# Sheet1.net
KiCad netlist of a schematic drawn in Altium Designer
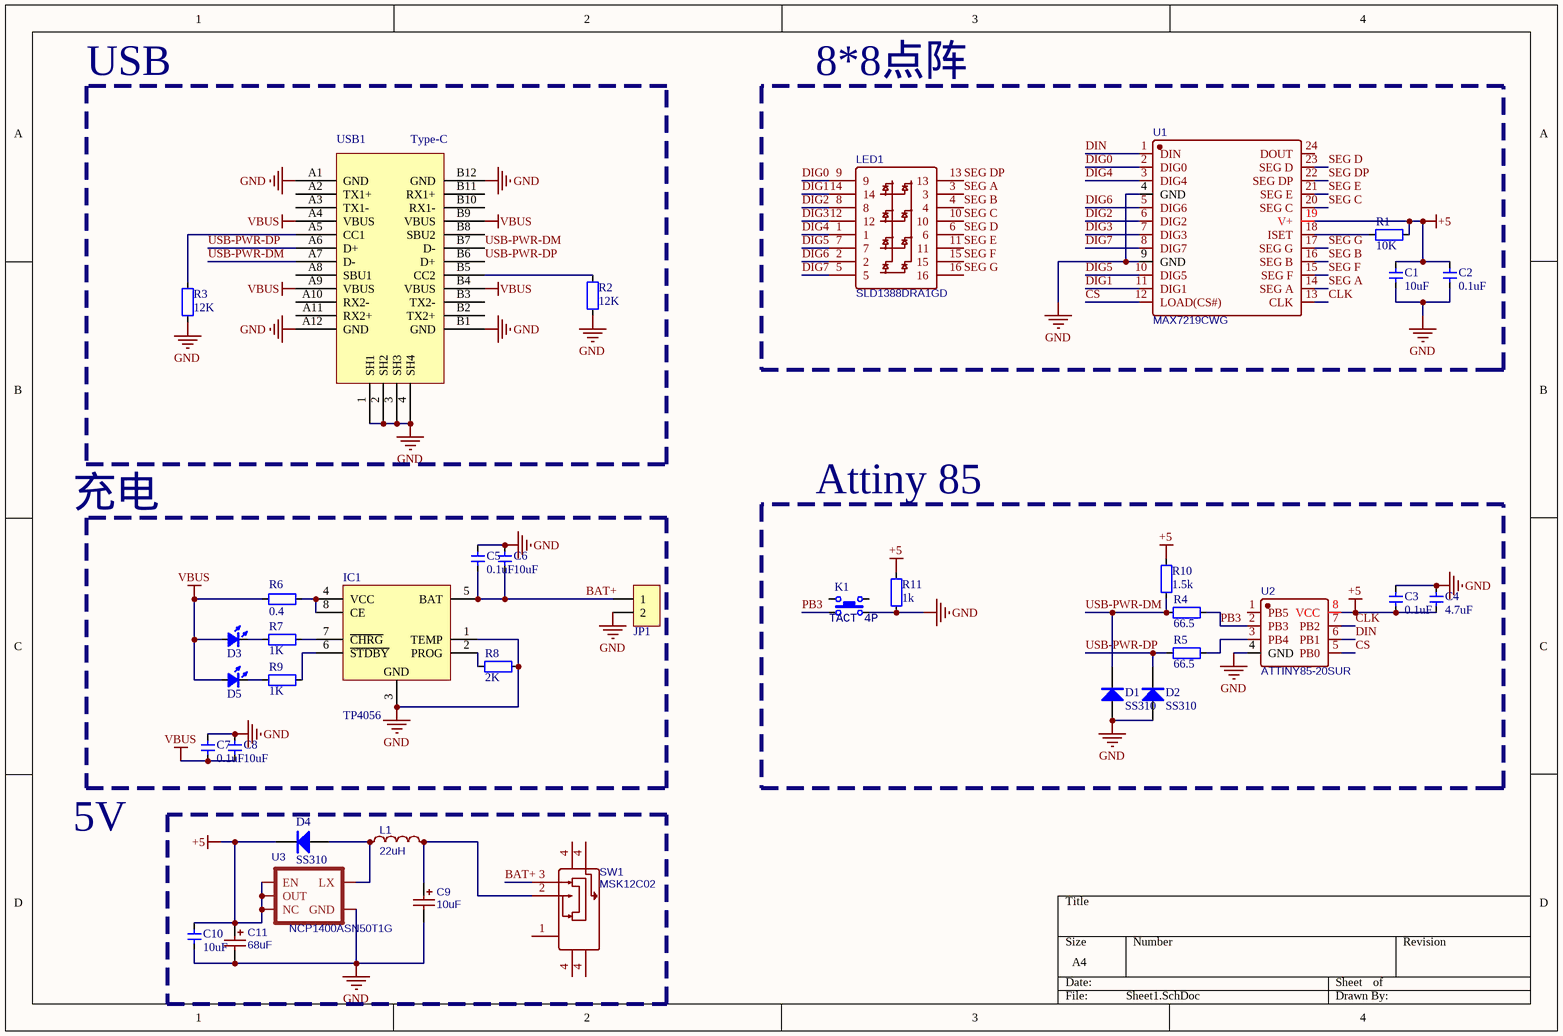
[diagram p0: Sheet1.SchDoc]

(export (version "E")
  (design (tool "Eeschema 10.0.6"))
  (components
    (comp (ref "C1")
      (value "10uF")
      (footprint "CAP_0402")
      (description "Capacitor")
      (libsource (lib "88DianZhen") (part "电容-0402"))
    )
    (comp (ref "C2")
      (value "0.1uF")
      (footprint "CAP_0402")
      (description "Capacitor")
      (libsource (lib "88DianZhen") (part "电容-0402"))
    )
    (comp (ref "C3")
      (value "0.1uF")
      (footprint "CAP_0402")
      (description "Capacitor")
      (libsource (lib "88DianZhen") (part "电容-0402"))
    )
    (comp (ref "C4")
      (value "4.7uF")
      (footprint "CAP_0402")
      (description "Capacitor")
      (libsource (lib "88DianZhen") (part "电容-0402"))
    )
    (comp (ref "C5")
      (value "0.1uF")
      (footprint "CAP_0402")
      (description "Capacitor")
      (libsource (lib "88DianZhen") (part "电容-0402"))
    )
    (comp (ref "C6")
      (value "10uF")
      (footprint "CAP_0402")
      (description "Capacitor")
      (libsource (lib "88DianZhen") (part "电容-0402"))
    )
    (comp (ref "C7")
      (value "0.1uF")
      (footprint "CAP_0402")
      (description "Capacitor")
      (libsource (lib "88DianZhen") (part "电容-0402"))
    )
    (comp (ref "C8")
      (value "10uF")
      (footprint "CAP_0402")
      (description "Capacitor")
      (libsource (lib "88DianZhen") (part "电容-0402"))
    )
    (comp (ref "C9")
      (value "10uF")
      (footprint "CAP-SMD_L3.2-W1.6-RD")
      (fields
        (field (name "BOM_MANUFACTURER PART") "CA45-A010M106T")
        (field (name "BOM_SUPPLIER PART") "C127946")
        (field (name "CONTRIBUTOR") "LCSC")
      )
      (libsource (lib "88DianZhen") (part "钽电容"))
    )
    (comp (ref "C10")
      (value "10uF")
      (footprint "CAP_0402")
      (description "Capacitor")
      (libsource (lib "88DianZhen") (part "电容-0402"))
    )
    (comp (ref "C11")
      (value "68uF")
      (footprint "CAP-SMD_L3.5-W2.8")
      (fields
        (field (name "BOM_MANUFACTURER PART") "CA45-A010M106T")
        (field (name "BOM_SUPPLIER PART") "C127946")
        (field (name "CONTRIBUTOR") "LCSC")
      )
      (libsource (lib "88DianZhen") (part "钽电容"))
    )
    (comp (ref "D1")
      (value "SS310")
      (footprint "SMA")
      (description "肖特基二极管")
      (fields (field (name "版权归属") "源创客"))
      (libsource (lib "88DianZhen") (part "SS210"))
    )
    (comp (ref "D2")
      (value "SS310")
      (footprint "SMA")
      (description "肖特基二极管")
      (fields (field (name "版权归属") "源创客"))
      (libsource (lib "88DianZhen") (part "SS210"))
    )
    (comp (ref "D3")
      (value "color?")
      (footprint "LED_0402_RED")
      (description "LED")
      (libsource (lib "88DianZhen") (part "LED_0402"))
    )
    (comp (ref "D4")
      (value "SS310")
      (footprint "SMA")
      (description "肖特基二极管")
      (fields (field (name "版权归属") "源创客"))
      (libsource (lib "88DianZhen") (part "二极管"))
    )
    (comp (ref "D5")
      (value "color?")
      (footprint "LED_0402_RED")
      (description "LED")
      (libsource (lib "88DianZhen") (part "LED_0402"))
    )
    (comp (ref "IC1")
      (value "TP4056")
      (footprint "PcbLib1:SOP8")
      (description "锂电池充电管理")
      (fields (field (name "版权归属") "源创客"))
      (libsource (lib "88DianZhen") (part "TP4056"))
    )
    (comp (ref "JP1")
      (value "HDR-1X2")
      (footprint "KF2EDGK-2.54-LI-2P")
      (description "2P接插件")
      (fields (field (name "版权归属") "源创客"))
      (libsource (lib "88DianZhen") (part "Header 2"))
    )
    (comp (ref "K1")
      (value "TACT 4P")
      (footprint "ButtonTACT_3.5*3.55_90")
      (description "Button")
      (fields (field (name "TYPE") "TACT 4P"))
      (libsource (lib "88DianZhen") (part "ButtonTACT"))
    )
    (comp (ref "L1")
      (value "22uH")
      (footprint "IND-SMD_L4.5-W4.0_SCD0403T")
      (fields
        (field (name "BOM_SUPPLIER PART") "C304283")
        (field (name "BOM_MANUFACTURER PART") "FPI0403F-220M")
        (field (name "CONTRIBUTOR") "LCSC")
      )
      (libsource (lib "88DianZhen") (part "电感"))
    )
    (comp (ref "LED1")
      (value "SLD1388DRA1GD")
      (footprint "8*8点阵")
      (fields (field (name "BOM_SUPPLIER PART") "C225991") (field (name "CONTRIBUTOR") "LCSC"))
      (libsource (lib "88DianZhen") (part "SLD1388DRA1GD"))
    )
    (comp (ref "R1")
      (value "10K")
      (footprint "R_0402")
      (description "Resistor")
      (libsource (lib "") (part "电阻-0402_1"))
    )
    (comp (ref "R2")
      (value "12K")
      (footprint "R_0402")
      (description "Resistor")
      (libsource (lib "88DianZhen") (part "电阻-0402"))
    )
    (comp (ref "R3")
      (value "12K")
      (footprint "R_0402")
      (description "Resistor")
      (libsource (lib "88DianZhen") (part "电阻-0402"))
    )
    (comp (ref "R4")
      (value "66.5")
      (footprint "0603R")
      (description "Resistor")
      (libsource (lib "") (part "电阻-0402_1"))
    )
    (comp (ref "R5")
      (value "66.5")
      (footprint "0603R")
      (description "Resistor")
      (libsource (lib "") (part "电阻-0402_1"))
    )
    (comp (ref "R6")
      (value "0.4")
      (footprint "1210R")
      (description "Resistor")
      (libsource (lib "") (part "电阻-0402_3"))
    )
    (comp (ref "R7")
      (value "1K")
      (footprint "R_0402")
      (description "Resistor")
      (libsource (lib "") (part "电阻-0402_1"))
    )
    (comp (ref "R8")
      (value "2K")
      (footprint "R_0402")
      (description "Resistor")
      (libsource (lib "") (part "电阻-0402_1"))
    )
    (comp (ref "R9")
      (value "1K")
      (footprint "R_0402")
      (description "Resistor")
      (libsource (lib "") (part "电阻-0402_1"))
    )
    (comp (ref "R10")
      (value "1.5k")
      (footprint "R_0402")
      (description "Resistor")
      (libsource (lib "") (part "电阻-0402_2"))
    )
    (comp (ref "R11")
      (value "1k")
      (footprint "R_0402")
      (description "Resistor")
      (libsource (lib "") (part "电阻-0402_2"))
    )
    (comp (ref "SW1")
      (value "MSK12C02")
      (footprint "SW-TH_MSK12C02")
      (fields (field (name "BOM_SUPPLIER PART") "C431540") (field (name "CONTRIBUTOR") "LCSC"))
      (libsource (lib "88DianZhen") (part "MSK12C02"))
    )
    (comp (ref "U1")
      (value "MAX7219CWG")
      (footprint "SOIC-24_L15.4-W7.5-P1.27-LS10.3-BL")
      (fields (field (name "BOM_SUPPLIER PART") "C9964"))
      (libsource (lib "88DianZhen") (part "MAX7219CWG"))
    )
    (comp (ref "U2")
      (value "ATTINY85-20SUR")
      (footprint "SOIC-8_L5.3-W5.3-P1.27-LS8.2-BL")
      (fields (field (name "BOM_SUPPLIER PART") "C2693737") (field (name "CONTRIBUTOR") "LCSC"))
      (libsource (lib "88DianZhen") (part "ATTINY85-20SUR"))
    )
    (comp (ref "U3")
      (value "NCP1400ASN50T1G")
      (footprint "SOT23-5")
      (fields (field (name "CONTRIBUTOR") "SparkFun"))
      (libsource (lib "88DianZhen") (part "NCP1400ASN50T1G"))
    )
    (comp (ref "USB1")
      (value "Type-C")
      (footprint "Type-C-TOP")
      (libsource (lib "88DianZhen") (part "USB-Type-C-TOP"))
    )
  )
  (nets
    (net (code "1") (name "+5") (class "Default")
      (node (ref "C1") (pin "2") (pinfunction "2_2") (pintype "passive"))
      (node (ref "C10") (pin "2") (pinfunction "2_2") (pintype "passive"))
      (node (ref "C11") (pin "1") (pinfunction "1_1") (pintype "passive"))
      (node (ref "C2") (pin "2") (pinfunction "2_2") (pintype "passive"))
      (node (ref "C3") (pin "1") (pinfunction "1_1") (pintype "passive"))
      (node (ref "C4") (pin "1") (pinfunction "1_1") (pintype "passive"))
      (node (ref "D4") (pin "2") (pinfunction "K_2") (pintype "passive"))
      (node (ref "R1") (pin "2") (pinfunction "2_2") (pintype "passive"))
      (node (ref "R10") (pin "2") (pinfunction "2_2") (pintype "passive"))
      (node (ref "R11") (pin "2") (pinfunction "2_2") (pintype "passive"))
      (node (ref "U1") (pin "19") (pinfunction "V+_19") (pintype "passive"))
      (node (ref "U2") (pin "8") (pinfunction "VCC_8") (pintype "passive"))
      (node (ref "U3") (pin "1") (pinfunction "EN_1") (pintype "passive"))
      (node (ref "U3") (pin "2") (pinfunction "OUT_2") (pintype "passive"))
      (node (ref "U3") (pin "3") (pinfunction "NC_3") (pintype "passive"))
    )
    (net (code "2") (name "/BAT+") (class "Default")
      (node (ref "C5") (pin "1") (pinfunction "1_1") (pintype "passive"))
      (node (ref "C6") (pin "1") (pinfunction "1_1") (pintype "passive"))
      (node (ref "IC1") (pin "5") (pinfunction "BAT_5") (pintype "passive"))
      (node (ref "JP1") (pin "1") (pinfunction "1_1") (pintype "passive"))
      (node (ref "SW1") (pin "3") (pinfunction "3_3") (pintype "passive"))
    )
    (net (code "3") (name "/CLK") (class "Default")
      (node (ref "U1") (pin "13") (pinfunction "CLK_13") (pintype "passive"))
      (node (ref "U2") (pin "7") (pinfunction "PB2_7") (pintype "passive"))
    )
    (net (code "4") (name "/CS") (class "Default")
      (node (ref "U1") (pin "12") (pinfunction "LOAD(CS#)_12") (pintype "passive"))
      (node (ref "U2") (pin "5") (pinfunction "PB0_5") (pintype "passive"))
    )
    (net (code "5") (name "/DIG0") (class "Default")
      (node (ref "LED1") (pin "9") (pinfunction "9_9") (pintype "passive"))
      (node (ref "U1") (pin "2") (pinfunction "DIG0_2") (pintype "passive"))
    )
    (net (code "6") (name "/DIG1") (class "Default")
      (node (ref "LED1") (pin "14") (pinfunction "14_14") (pintype "passive"))
      (node (ref "U1") (pin "11") (pinfunction "DIG1_11") (pintype "passive"))
    )
    (net (code "7") (name "/DIG2") (class "Default")
      (node (ref "LED1") (pin "8") (pinfunction "8_8") (pintype "passive"))
      (node (ref "U1") (pin "6") (pinfunction "DIG2_6") (pintype "passive"))
    )
    (net (code "8") (name "/DIG3") (class "Default")
      (node (ref "LED1") (pin "12") (pinfunction "12_12") (pintype "passive"))
      (node (ref "U1") (pin "7") (pinfunction "DIG3_7") (pintype "passive"))
    )
    (net (code "9") (name "/DIG4") (class "Default")
      (node (ref "LED1") (pin "1") (pinfunction "1_1") (pintype "passive"))
      (node (ref "U1") (pin "3") (pinfunction "DIG4_3") (pintype "passive"))
    )
    (net (code "10") (name "/DIG5") (class "Default")
      (node (ref "LED1") (pin "7") (pinfunction "7_7") (pintype "passive"))
      (node (ref "U1") (pin "10") (pinfunction "DIG5_10") (pintype "passive"))
    )
    (net (code "11") (name "/DIG6") (class "Default")
      (node (ref "LED1") (pin "2") (pinfunction "2_2") (pintype "passive"))
      (node (ref "U1") (pin "5") (pinfunction "DIG6_5") (pintype "passive"))
    )
    (net (code "12") (name "/DIG7") (class "Default")
      (node (ref "LED1") (pin "5") (pinfunction "5_5") (pintype "passive"))
      (node (ref "U1") (pin "8") (pinfunction "DIG7_8") (pintype "passive"))
    )
    (net (code "13") (name "/DIN") (class "Default")
      (node (ref "U1") (pin "1") (pinfunction "DIN_1") (pintype "passive"))
      (node (ref "U2") (pin "6") (pinfunction "PB1_6") (pintype "passive"))
    )
    (net (code "14") (name "/PB3") (class "Default")
      (node (ref "K1") (pin "3") (pinfunction "3_3") (pintype "passive"))
      (node (ref "R4") (pin "2") (pinfunction "2_2") (pintype "passive"))
      (node (ref "U2") (pin "2") (pinfunction "PB3_2") (pintype "passive"))
    )
    (net (code "15") (name "/SEG A") (class "Default")
      (node (ref "LED1") (pin "3") (pinfunction "3_3") (pintype "passive"))
      (node (ref "U1") (pin "14") (pinfunction "SEG_A_14") (pintype "passive"))
    )
    (net (code "16") (name "/SEG B") (class "Default")
      (node (ref "LED1") (pin "4") (pinfunction "4_4") (pintype "passive"))
      (node (ref "U1") (pin "16") (pinfunction "SEG_B_16") (pintype "passive"))
    )
    (net (code "17") (name "/SEG C") (class "Default")
      (node (ref "LED1") (pin "10") (pinfunction "10_10") (pintype "passive"))
      (node (ref "U1") (pin "20") (pinfunction "SEG_C_20") (pintype "passive"))
    )
    (net (code "18") (name "/SEG D") (class "Default")
      (node (ref "LED1") (pin "6") (pinfunction "6_6") (pintype "passive"))
      (node (ref "U1") (pin "23") (pinfunction "SEG_D_23") (pintype "passive"))
    )
    (net (code "19") (name "/SEG DP") (class "Default")
      (node (ref "LED1") (pin "13") (pinfunction "13_13") (pintype "passive"))
      (node (ref "U1") (pin "22") (pinfunction "SEG_DP_22") (pintype "passive"))
    )
    (net (code "20") (name "/SEG E") (class "Default")
      (node (ref "LED1") (pin "11") (pinfunction "11_11") (pintype "passive"))
      (node (ref "U1") (pin "21") (pinfunction "SEG_E_21") (pintype "passive"))
    )
    (net (code "21") (name "/SEG F") (class "Default")
      (node (ref "LED1") (pin "15") (pinfunction "15_15") (pintype "passive"))
      (node (ref "U1") (pin "15") (pinfunction "SEG_F_15") (pintype "passive"))
    )
    (net (code "22") (name "/SEG G") (class "Default")
      (node (ref "LED1") (pin "16") (pinfunction "16_16") (pintype "passive"))
      (node (ref "U1") (pin "17") (pinfunction "SEG_G_17") (pintype "passive"))
    )
    (net (code "23") (name "/USB-PWR-DM") (class "Default")
      (node (ref "D1") (pin "2") (pinfunction "K_2") (pintype "passive"))
      (node (ref "R10") (pin "1") (pinfunction "1_1") (pintype "passive"))
      (node (ref "R4") (pin "1") (pinfunction "1_1") (pintype "passive"))
      (node (ref "USB1") (pin "A7") (pinfunction "D-_A7") (pintype "passive"))
      (node (ref "USB1") (pin "B7") (pinfunction "D-_B7") (pintype "passive"))
    )
    (net (code "24") (name "/USB-PWR-DP") (class "Default")
      (node (ref "D2") (pin "2") (pinfunction "K_2") (pintype "passive"))
      (node (ref "R5") (pin "1") (pinfunction "1_1") (pintype "passive"))
      (node (ref "USB1") (pin "A6") (pinfunction "D+_A6") (pintype "passive"))
      (node (ref "USB1") (pin "B6") (pinfunction "D+_B6") (pintype "passive"))
    )
    (net (code "25") (name "GND") (class "Default")
      (node (ref "C1") (pin "1") (pinfunction "1_1") (pintype "passive"))
      (node (ref "C10") (pin "1") (pinfunction "1_1") (pintype "passive"))
      (node (ref "C11") (pin "2") (pinfunction "2_2") (pintype "passive"))
      (node (ref "C2") (pin "1") (pinfunction "1_1") (pintype "passive"))
      (node (ref "C3") (pin "2") (pinfunction "2_2") (pintype "passive"))
      (node (ref "C4") (pin "2") (pinfunction "2_2") (pintype "passive"))
      (node (ref "C5") (pin "2") (pinfunction "2_2") (pintype "passive"))
      (node (ref "C6") (pin "2") (pinfunction "2_2") (pintype "passive"))
      (node (ref "C7") (pin "2") (pinfunction "2_2") (pintype "passive"))
      (node (ref "C8") (pin "2") (pinfunction "2_2") (pintype "passive"))
      (node (ref "C9") (pin "2") (pinfunction "2_2") (pintype "passive"))
      (node (ref "D1") (pin "1") (pinfunction "A_1") (pintype "passive"))
      (node (ref "D2") (pin "1") (pinfunction "A_1") (pintype "passive"))
      (node (ref "IC1") (pin "1") (pinfunction "TEMP_1") (pintype "passive"))
      (node (ref "IC1") (pin "3") (pinfunction "GND_3") (pintype "passive"))
      (node (ref "JP1") (pin "2") (pinfunction "2_2") (pintype "passive"))
      (node (ref "K1") (pin "4") (pinfunction "4_4") (pintype "passive"))
      (node (ref "R11") (pin "1") (pinfunction "1_1") (pintype "passive"))
      (node (ref "R2") (pin "2") (pinfunction "2_2") (pintype "passive"))
      (node (ref "R3") (pin "2") (pinfunction "2_2") (pintype "passive"))
      (node (ref "R8") (pin "2") (pinfunction "2_2") (pintype "passive"))
      (node (ref "U1") (pin "4") (pinfunction "GND_4") (pintype "passive"))
      (node (ref "U1") (pin "9") (pinfunction "GND_9") (pintype "passive"))
      (node (ref "U2") (pin "4") (pinfunction "GND_4") (pintype "passive"))
      (node (ref "U3") (pin "4") (pinfunction "GND_4") (pintype "passive"))
      (node (ref "USB1") (pin "1") (pinfunction "SH1_1") (pintype "passive"))
      (node (ref "USB1") (pin "2") (pinfunction "SH2_2") (pintype "passive"))
      (node (ref "USB1") (pin "3") (pinfunction "SH3_3") (pintype "passive"))
      (node (ref "USB1") (pin "4") (pinfunction "SH4_4") (pintype "passive"))
      (node (ref "USB1") (pin "A1") (pinfunction "GND_A1") (pintype "passive"))
      (node (ref "USB1") (pin "A12") (pinfunction "GND_A12") (pintype "passive"))
      (node (ref "USB1") (pin "B1") (pinfunction "GND_B1") (pintype "passive"))
      (node (ref "USB1") (pin "B12") (pinfunction "GND_B12") (pintype "passive"))
    )
    (net (code "26") (name "Net-(C9-Pad1)") (class "Default")
      (node (ref "C9") (pin "1") (pinfunction "1_1") (pintype "passive"))
      (node (ref "L1") (pin "2") (pinfunction "2_2") (pintype "passive"))
      (node (ref "SW1") (pin "2") (pinfunction "2_2") (pintype "passive"))
    )
    (net (code "27") (name "Net-(D3-K)") (class "Default")
      (node (ref "D3") (pin "2") (pinfunction "K_2") (pintype "passive"))
      (node (ref "R7") (pin "1") (pinfunction "1_1") (pintype "passive"))
    )
    (net (code "28") (name "Net-(D4-A)") (class "Default")
      (node (ref "D4") (pin "1") (pinfunction "A_1") (pintype "passive"))
      (node (ref "L1") (pin "1") (pinfunction "1_1") (pintype "passive"))
      (node (ref "U3") (pin "5") (pinfunction "LX_5") (pintype "passive"))
    )
    (net (code "29") (name "Net-(D5-K)") (class "Default")
      (node (ref "D5") (pin "2") (pinfunction "K_2") (pintype "passive"))
      (node (ref "R9") (pin "1") (pinfunction "1_1") (pintype "passive"))
    )
    (net (code "30") (name "Net-(IC1-CE)") (class "Default")
      (node (ref "IC1") (pin "4") (pinfunction "VCC_4") (pintype "passive"))
      (node (ref "IC1") (pin "8") (pinfunction "CE_8") (pintype "passive"))
      (node (ref "R6") (pin "1") (pinfunction "1_1") (pintype "passive"))
    )
    (net (code "31") (name "Net-(IC1-PROG)") (class "Default")
      (node (ref "IC1") (pin "2") (pinfunction "PROG_2") (pintype "passive"))
      (node (ref "R8") (pin "1") (pinfunction "1_1") (pintype "passive"))
    )
    (net (code "32") (name "Net-(IC1-~{CHRG})") (class "Default")
      (node (ref "IC1") (pin "7") (pinfunction "~{CHRG}_7") (pintype "passive"))
      (node (ref "R7") (pin "2") (pinfunction "2_2") (pintype "passive"))
    )
    (net (code "33") (name "Net-(IC1-~{STDBY})") (class "Default")
      (node (ref "IC1") (pin "6") (pinfunction "~{STDBY}_6") (pintype "passive"))
      (node (ref "R9") (pin "2") (pinfunction "2_2") (pintype "passive"))
    )
    (net (code "34") (name "Net-(U1-ISET)") (class "Default")
      (node (ref "R1") (pin "1") (pinfunction "1_1") (pintype "passive"))
      (node (ref "U1") (pin "18") (pinfunction "ISET_18") (pintype "passive"))
    )
    (net (code "35") (name "Net-(U2-PB4)") (class "Default")
      (node (ref "R5") (pin "2") (pinfunction "2_2") (pintype "passive"))
      (node (ref "U2") (pin "3") (pinfunction "PB4_3") (pintype "passive"))
    )
    (net (code "36") (name "Net-(USB1-CC1)") (class "Default")
      (node (ref "R3") (pin "1") (pinfunction "1_1") (pintype "passive"))
      (node (ref "USB1") (pin "A5") (pinfunction "CC1_A5") (pintype "passive"))
    )
    (net (code "37") (name "Net-(USB1-CC2)") (class "Default")
      (node (ref "R2") (pin "1") (pinfunction "1_1") (pintype "passive"))
      (node (ref "USB1") (pin "B5") (pinfunction "CC2_B5") (pintype "passive"))
    )
    (net (code "38") (name "VBUS") (class "Default")
      (node (ref "C7") (pin "1") (pinfunction "1_1") (pintype "passive"))
      (node (ref "C8") (pin "1") (pinfunction "1_1") (pintype "passive"))
      (node (ref "D3") (pin "1") (pinfunction "A_1") (pintype "passive"))
      (node (ref "D5") (pin "1") (pinfunction "A_1") (pintype "passive"))
      (node (ref "R6") (pin "2") (pinfunction "2_2") (pintype "passive"))
      (node (ref "USB1") (pin "A4") (pinfunction "VBUS_A4") (pintype "passive"))
      (node (ref "USB1") (pin "A9") (pinfunction "VBUS_A9") (pintype "passive"))
      (node (ref "USB1") (pin "B4") (pinfunction "VBUS_B4") (pintype "passive"))
      (node (ref "USB1") (pin "B9") (pinfunction "VBUS_B9") (pintype "passive"))
    )
    (net (code "39") (name "unconnected-(K1-Pad1)") (class "Default")
      (node (ref "K1") (pin "1") (pinfunction "1_1") (pintype "passive"))
    )
    (net (code "40") (name "unconnected-(K1-Pad2)") (class "Default")
      (node (ref "K1") (pin "2") (pinfunction "2_2") (pintype "passive"))
    )
    (net (code "41") (name "unconnected-(SW1-Pad1)") (class "Default")
      (node (ref "SW1") (pin "1") (pinfunction "1_1") (pintype "passive"))
    )
    (net (code "42") (name "unconnected-(SW1-Pad4)") (class "Default")
      (node (ref "SW1") (pin "4") (pinfunction "4_4") (pintype "passive"))
    )
    (net (code "43") (name "unconnected-(SW1-Pad4)_1") (class "Default")
      (node (ref "SW1") (pin "4") (pinfunction "4_4") (pintype "passive"))
    )
    (net (code "44") (name "unconnected-(SW1-Pad4)_2") (class "Default")
      (node (ref "SW1") (pin "4") (pinfunction "4_4") (pintype "passive"))
    )
    (net (code "45") (name "unconnected-(SW1-Pad4)_3") (class "Default")
      (node (ref "SW1") (pin "4") (pinfunction "4_4") (pintype "passive"))
    )
    (net (code "46") (name "unconnected-(U1-DOUT-Pad24)") (class "Default")
      (node (ref "U1") (pin "24") (pinfunction "DOUT_24") (pintype "passive"))
    )
    (net (code "47") (name "unconnected-(U2-PB5-Pad1)") (class "Default")
      (node (ref "U2") (pin "1") (pinfunction "PB5_1") (pintype "passive"))
    )
    (net (code "48") (name "unconnected-(USB1-RX1+-PadB11)") (class "Default")
      (node (ref "USB1") (pin "B11") (pinfunction "RX1+_B11") (pintype "passive"))
    )
    (net (code "49") (name "unconnected-(USB1-RX1--PadB10)") (class "Default")
      (node (ref "USB1") (pin "B10") (pinfunction "RX1-_B10") (pintype "passive"))
    )
    (net (code "50") (name "unconnected-(USB1-RX2+-PadA11)") (class "Default")
      (node (ref "USB1") (pin "A11") (pinfunction "RX2+_A11") (pintype "passive"))
    )
    (net (code "51") (name "unconnected-(USB1-RX2--PadA10)") (class "Default")
      (node (ref "USB1") (pin "A10") (pinfunction "RX2-_A10") (pintype "passive"))
    )
    (net (code "52") (name "unconnected-(USB1-SBU1-PadA8)") (class "Default")
      (node (ref "USB1") (pin "A8") (pinfunction "SBU1_A8") (pintype "passive"))
    )
    (net (code "53") (name "unconnected-(USB1-SBU2-PadB8)") (class "Default")
      (node (ref "USB1") (pin "B8") (pinfunction "SBU2_B8") (pintype "passive"))
    )
    (net (code "54") (name "unconnected-(USB1-TX1+-PadA2)") (class "Default")
      (node (ref "USB1") (pin "A2") (pinfunction "TX1+_A2") (pintype "passive"))
    )
    (net (code "55") (name "unconnected-(USB1-TX1--PadA3)") (class "Default")
      (node (ref "USB1") (pin "A3") (pinfunction "TX1-_A3") (pintype "passive"))
    )
    (net (code "56") (name "unconnected-(USB1-TX2+-PadB2)") (class "Default")
      (node (ref "USB1") (pin "B2") (pinfunction "TX2+_B2") (pintype "passive"))
    )
    (net (code "57") (name "unconnected-(USB1-TX2--PadB3)") (class "Default")
      (node (ref "USB1") (pin "B3") (pinfunction "TX2-_B3") (pintype "passive"))
    )
  )
)
